# RS233_BRD_single.net
KiCad netlist of a schematic drawn in EAGLE
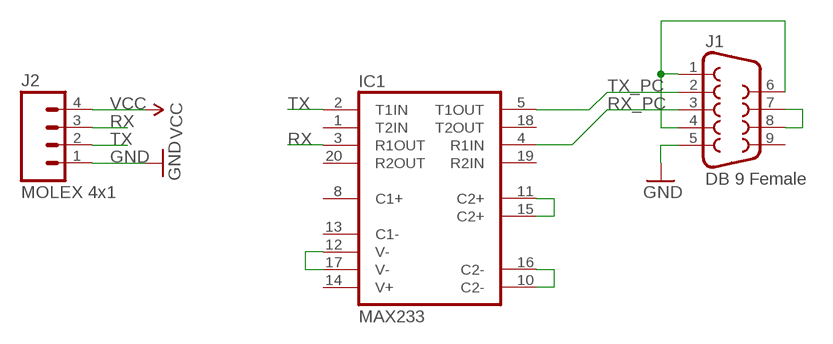
[diagram p0: schematic, sheet 1]

(export (version "E")
  (design (tool "Eeschema 10.0.6"))
  (components
    (comp (ref "IC1")
      (value "MAX233")
      (footprint "eagle-import:DIL20")
      (fields (field (name "MPN") "MAX233ACPP+G36"))
      (libsource (lib "eagle-import") (part "MAX233"))
    )
    (comp (ref "J1")
      (value "DB 9 Female")
      (footprint "eagle-import:DB9")
      (libsource (lib "eagle-import") (part "DB9FEMALE"))
    )
    (comp (ref "J2")
      (value "MOLEX 4x1")
      (footprint "eagle-import:MOLEX-1X4")
      (libsource (lib "eagle-import") (part "M04POLAR"))
    )
  )
  (nets
    (net (code "1") (name "/RX") (class "Default")
      (node (ref "IC1") (pin "3") (pinfunction "R1OUT_3") (pintype "output"))
      (node (ref "J2") (pin "3") (pinfunction "3_3") (pintype "passive"))
    )
    (net (code "2") (name "/RX_PC") (class "Default")
      (node (ref "IC1") (pin "4") (pinfunction "R1IN_4") (pintype "input"))
      (node (ref "J1") (pin "3") (pinfunction "3_3") (pintype "passive"))
    )
    (net (code "3") (name "/TX") (class "Default")
      (node (ref "IC1") (pin "2") (pinfunction "T1IN_2") (pintype "input"))
      (node (ref "J2") (pin "2") (pinfunction "2_2") (pintype "passive"))
    )
    (net (code "4") (name "/TX_PC") (class "Default")
      (node (ref "IC1") (pin "5") (pinfunction "T1OUT_5") (pintype "output"))
      (node (ref "J1") (pin "2") (pinfunction "2_2") (pintype "passive"))
    )
    (net (code "5") (name "GND") (class "Default")
      (node (ref "J1") (pin "5") (pinfunction "5_5") (pintype "passive"))
      (node (ref "J2") (pin "1") (pinfunction "1_1") (pintype "passive"))
    )
    (net (code "6") (name "Net-(IC1A-C2+-Pad11)") (class "Default")
      (node (ref "IC1") (pin "11") (pinfunction "C2+_11") (pintype "bidirectional"))
      (node (ref "IC1") (pin "15") (pinfunction "C2+_15") (pintype "bidirectional"))
    )
    (net (code "7") (name "Net-(IC1A-C2--Pad10)") (class "Default")
      (node (ref "IC1") (pin "10") (pinfunction "C2-_10") (pintype "bidirectional"))
      (node (ref "IC1") (pin "16") (pinfunction "C2-_16") (pintype "bidirectional"))
    )
    (net (code "8") (name "Net-(IC1A-V--Pad12)") (class "Default")
      (node (ref "IC1") (pin "12") (pinfunction "V-_12") (pintype "bidirectional"))
      (node (ref "IC1") (pin "17") (pinfunction "V-_17") (pintype "bidirectional"))
    )
    (net (code "9") (name "Net-(J1-Pad1)") (class "Default")
      (node (ref "J1") (pin "1") (pinfunction "1_1") (pintype "passive"))
      (node (ref "J1") (pin "4") (pinfunction "4_4") (pintype "passive"))
      (node (ref "J1") (pin "6") (pinfunction "6_6") (pintype "passive"))
    )
    (net (code "10") (name "Net-(J1-Pad7)") (class "Default")
      (node (ref "J1") (pin "7") (pinfunction "7_7") (pintype "passive"))
      (node (ref "J1") (pin "8") (pinfunction "8_8") (pintype "passive"))
    )
    (net (code "11") (name "VCC") (class "Default")
      (node (ref "J2") (pin "4") (pinfunction "4_4") (pintype "passive"))
    )
    (net (code "12") (name "unconnected-(IC1A-C1+-Pad8)") (class "Default")
      (node (ref "IC1") (pin "8") (pinfunction "C1+_8") (pintype "bidirectional"))
    )
    (net (code "13") (name "unconnected-(IC1A-C1--Pad13)") (class "Default")
      (node (ref "IC1") (pin "13") (pinfunction "C1-_13") (pintype "bidirectional"))
    )
    (net (code "14") (name "unconnected-(IC1A-R2IN-Pad19)") (class "Default")
      (node (ref "IC1") (pin "19") (pinfunction "R2IN_19") (pintype "input"))
    )
    (net (code "15") (name "unconnected-(IC1A-R2OUT-Pad20)") (class "Default")
      (node (ref "IC1") (pin "20") (pinfunction "R2OUT_20") (pintype "output"))
    )
    (net (code "16") (name "unconnected-(IC1A-T2IN-Pad1)") (class "Default")
      (node (ref "IC1") (pin "1") (pinfunction "T2IN_1") (pintype "input"))
    )
    (net (code "17") (name "unconnected-(IC1A-T2OUT-Pad18)") (class "Default")
      (node (ref "IC1") (pin "18") (pinfunction "T2OUT_18") (pintype "output"))
    )
    (net (code "18") (name "unconnected-(IC1A-V+-Pad14)") (class "Default")
      (node (ref "IC1") (pin "14") (pinfunction "V+_14") (pintype "bidirectional"))
    )
    (net (code "19") (name "unconnected-(J1-Pad9)") (class "Default")
      (node (ref "J1") (pin "9") (pinfunction "9_9") (pintype "passive"))
    )
  )
)
